# Esquema_v21.net
KiCad netlist of a schematic drawn in EAGLE
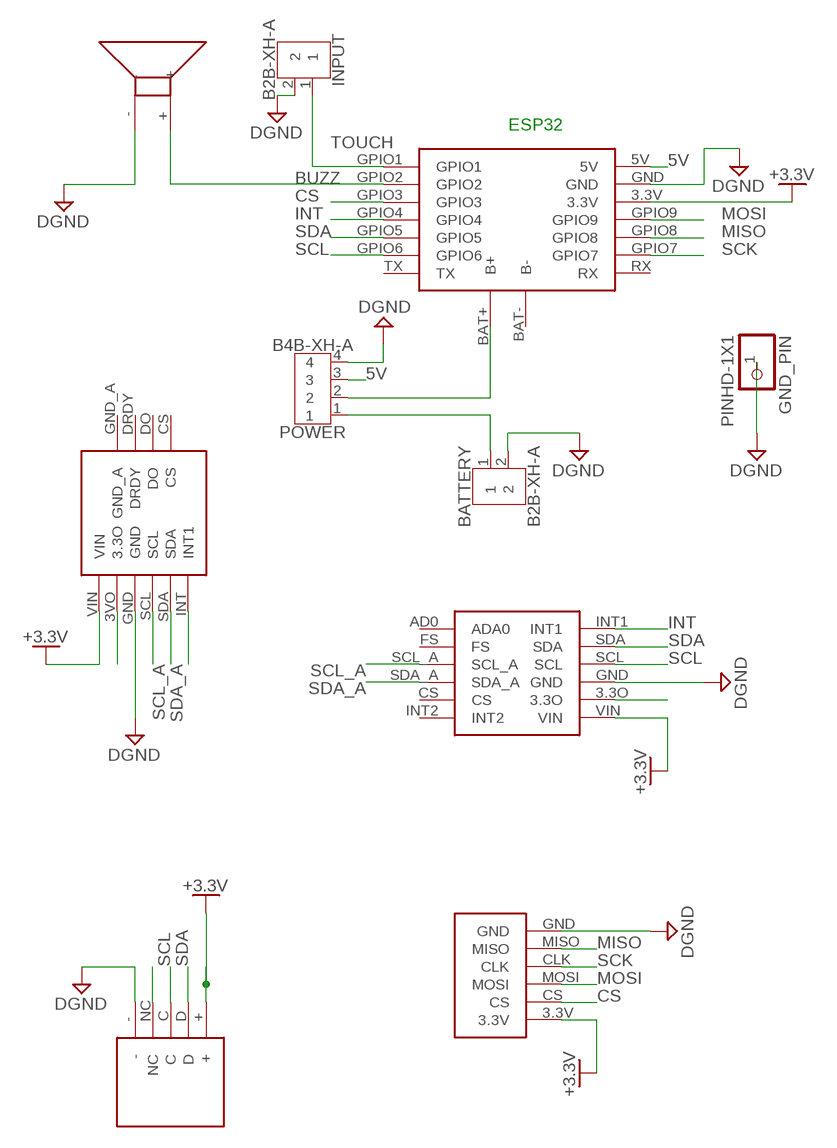
[diagram p0: schematic, sheet 1]

(export (version "E")
  (design (tool "Eeschema 10.0.6"))
  (components
    (comp (ref "BATTERY")
      (value "B2B-XH-A")
      (footprint "eagle-import:B2B-XH-A")
      (fields (field (name "MANUFACTURER") "JST Sales America Inc."))
      (libsource (lib "eagle-import") (part "B2B-XH-A"))
    )
    (comp (ref "GND_PIN")
      (value "PINHD-1X1")
      (footprint "eagle-import:1X01")
      (libsource (lib "eagle-import") (part "PINHD-1X1"))
    )
    (comp (ref "INPUT")
      (value "B2B-XH-A")
      (footprint "eagle-import:B2B-XH-A")
      (fields (field (name "MANUFACTURER") "JST Sales America Inc."))
      (libsource (lib "eagle-import") (part "B2B-XH-A"))
    )
    (comp (ref "POWER")
      (value "B4B-XH-A")
      (footprint "eagle-import:B4B-XH-A")
      (fields (field (name "MANUFACTURER") "JST Sales America Inc."))
      (libsource (lib "eagle-import") (part "B4B-XH-A"))
    )
    (comp (ref "U$1")
      (value "LIS3MDL")
      (footprint "eagle-import:LIS3MDL")
      (libsource (lib "eagle-import") (part "LIS3MDL"))
    )
    (comp (ref "U$2")
      (value "ICM20649")
      (footprint "eagle-import:ICM20649")
      (libsource (lib "eagle-import") (part "ICM20649"))
    )
    (comp (ref "U$3")
      (value "ESP32_SEEED_THP")
      (footprint "eagle-import:ESP32_SEEED_THP")
      (libsource (lib "eagle-import") (part "ESP32_SEEED_THP"))
    )
    (comp (ref "U$4")
      (value "DS3231_RPI")
      (footprint "eagle-import:DS3231_RPI")
      (libsource (lib "eagle-import") (part "DS3231_RPI"))
    )
    (comp (ref "U$5")
      (value "MICROSD_READER")
      (footprint "eagle-import:MICROSD_READER")
      (libsource (lib "eagle-import") (part "MICROSD_READER"))
    )
    (comp (ref "U$6")
      (value "BUZZER")
      (footprint "eagle-import:BUZZER")
      (libsource (lib "eagle-import") (part "BUZZER"))
    )
  )
  (nets
    (net (code "1") (name "+3.3V") (class "Default")
      (node (ref "U$1") (pin "VIN") (pinfunction "VIN_VIN") (pintype "bidirectional"))
      (node (ref "U$2") (pin "VIN") (pinfunction "VIN_VIN") (pintype "bidirectional"))
      (node (ref "U$3") (pin "3.3V") (pinfunction "3.3V_3.3V") (pintype "bidirectional"))
      (node (ref "U$4") (pin "+") (pinfunction "+_+") (pintype "bidirectional"))
      (node (ref "U$5") (pin "3.3V") (pinfunction "3.3V_3.3V") (pintype "bidirectional"))
    )
    (net (code "2") (name "/5V") (class "Default")
      (node (ref "POWER") (pin "3") (pinfunction "3_3") (pintype "bidirectional"))
      (node (ref "U$3") (pin "5V") (pinfunction "5V_5V") (pintype "bidirectional"))
    )
    (net (code "3") (name "/BUZZ") (class "Default")
      (node (ref "U$3") (pin "GPIO2") (pinfunction "GPIO2_GPIO2") (pintype "bidirectional"))
      (node (ref "U$6") (pin "+") (pinfunction "+_+") (pintype "bidirectional"))
    )
    (net (code "4") (name "/CS") (class "Default")
      (node (ref "U$3") (pin "GPIO3") (pinfunction "GPIO3_GPIO3") (pintype "bidirectional"))
      (node (ref "U$5") (pin "CS") (pinfunction "CS_CS") (pintype "bidirectional"))
    )
    (net (code "5") (name "/INT") (class "Default")
      (node (ref "U$2") (pin "INT1") (pinfunction "INT1_INT1") (pintype "bidirectional"))
      (node (ref "U$3") (pin "GPIO4") (pinfunction "GPIO4_GPIO4") (pintype "bidirectional"))
    )
    (net (code "6") (name "/MISO") (class "Default")
      (node (ref "U$3") (pin "GPIO8") (pinfunction "GPIO8_GPIO8") (pintype "bidirectional"))
      (node (ref "U$5") (pin "MISO") (pinfunction "MISO_MISO") (pintype "bidirectional"))
    )
    (net (code "7") (name "/MOSI") (class "Default")
      (node (ref "U$3") (pin "GPIO9") (pinfunction "GPIO9_GPIO9") (pintype "bidirectional"))
      (node (ref "U$5") (pin "MOSI") (pinfunction "MOSI_MOSI") (pintype "bidirectional"))
    )
    (net (code "8") (name "/SCK") (class "Default")
      (node (ref "U$3") (pin "GPIO7") (pinfunction "GPIO7_GPIO7") (pintype "bidirectional"))
      (node (ref "U$5") (pin "CLK") (pinfunction "CLK_CLK") (pintype "bidirectional"))
    )
    (net (code "9") (name "/SCL") (class "Default")
      (node (ref "U$2") (pin "SCL") (pinfunction "SCL_SCL") (pintype "bidirectional"))
      (node (ref "U$3") (pin "GPIO6") (pinfunction "GPIO6_GPIO6") (pintype "bidirectional"))
      (node (ref "U$4") (pin "C") (pinfunction "C_C") (pintype "bidirectional"))
    )
    (net (code "10") (name "/SCL_A") (class "Default")
      (node (ref "U$1") (pin "SCL") (pinfunction "SCL_SCL") (pintype "bidirectional"))
      (node (ref "U$2") (pin "SCL_A") (pinfunction "SCL_A_SCL_A") (pintype "bidirectional"))
    )
    (net (code "11") (name "/SDA") (class "Default")
      (node (ref "U$2") (pin "SDA") (pinfunction "SDA_SDA") (pintype "bidirectional"))
      (node (ref "U$3") (pin "GPIO5") (pinfunction "GPIO5_GPIO5") (pintype "bidirectional"))
      (node (ref "U$4") (pin "D") (pinfunction "D_D") (pintype "bidirectional"))
    )
    (net (code "12") (name "/SDA_A") (class "Default")
      (node (ref "U$1") (pin "SDA") (pinfunction "SDA_SDA") (pintype "bidirectional"))
      (node (ref "U$2") (pin "SDA_A") (pinfunction "SDA_A_SDA_A") (pintype "bidirectional"))
    )
    (net (code "13") (name "/TOUCH") (class "Default")
      (node (ref "INPUT") (pin "1") (pinfunction "1_1") (pintype "bidirectional"))
      (node (ref "U$3") (pin "GPIO1") (pinfunction "GPIO1_GPIO1") (pintype "bidirectional"))
    )
    (net (code "14") (name "DGND") (class "Default")
      (node (ref "BATTERY") (pin "2") (pinfunction "2_2") (pintype "bidirectional"))
      (node (ref "GND_PIN") (pin "1") (pinfunction "1_1") (pintype "passive"))
      (node (ref "INPUT") (pin "2") (pinfunction "2_2") (pintype "bidirectional"))
      (node (ref "POWER") (pin "4") (pinfunction "4_4") (pintype "bidirectional"))
      (node (ref "U$1") (pin "GND") (pinfunction "GND_GND") (pintype "bidirectional"))
      (node (ref "U$2") (pin "GND") (pinfunction "GND_GND") (pintype "bidirectional"))
      (node (ref "U$3") (pin "GND") (pinfunction "GND_GND") (pintype "bidirectional"))
      (node (ref "U$4") (pin "-") (pinfunction "-_-") (pintype "bidirectional"))
      (node (ref "U$5") (pin "GND") (pinfunction "GND_GND") (pintype "bidirectional"))
      (node (ref "U$6") (pin "-") (pinfunction "-_-") (pintype "bidirectional"))
    )
    (net (code "15") (name "Net-(BATTERY-Pad1)") (class "Default")
      (node (ref "BATTERY") (pin "1") (pinfunction "1_1") (pintype "bidirectional"))
      (node (ref "POWER") (pin "1") (pinfunction "1_1") (pintype "bidirectional"))
    )
    (net (code "16") (name "Net-(U$3-B+)") (class "Default")
      (node (ref "POWER") (pin "2") (pinfunction "2_2") (pintype "bidirectional"))
      (node (ref "U$3") (pin "BAT+") (pinfunction "B+_BAT+") (pintype "bidirectional"))
    )
    (net (code "17") (name "unconnected-(U$1-3.3O-Pad3VO)") (class "Default")
      (node (ref "U$1") (pin "3VO") (pinfunction "3.3O_3VO") (pintype "bidirectional"))
    )
    (net (code "18") (name "unconnected-(U$1-INT1-PadINT)") (class "Default")
      (node (ref "U$1") (pin "INT") (pinfunction "INT1_INT") (pintype "bidirectional"))
    )
    (net (code "19") (name "unconnected-(U$1-PadCS)") (class "Default")
      (node (ref "U$1") (pin "CS") (pinfunction "CS_CS") (pintype "bidirectional"))
    )
    (net (code "20") (name "unconnected-(U$1-PadDO)") (class "Default")
      (node (ref "U$1") (pin "DO") (pinfunction "DO_DO") (pintype "bidirectional"))
    )
    (net (code "21") (name "unconnected-(U$1-PadDRDY)") (class "Default")
      (node (ref "U$1") (pin "DRDY") (pinfunction "DRDY_DRDY") (pintype "bidirectional"))
    )
    (net (code "22") (name "unconnected-(U$1-PadGND_A)") (class "Default")
      (node (ref "U$1") (pin "GND_A") (pinfunction "GND_A_GND_A") (pintype "bidirectional"))
    )
    (net (code "23") (name "unconnected-(U$2-ADA0-PadAD0)") (class "Default")
      (node (ref "U$2") (pin "AD0") (pinfunction "ADA0_AD0") (pintype "bidirectional"))
    )
    (net (code "24") (name "unconnected-(U$2-Pad3.3O)") (class "Default")
      (node (ref "U$2") (pin "3.3O") (pinfunction "3.3O_3.3O") (pintype "bidirectional"))
    )
    (net (code "25") (name "unconnected-(U$2-PadCS)") (class "Default")
      (node (ref "U$2") (pin "CS") (pinfunction "CS_CS") (pintype "bidirectional"))
    )
    (net (code "26") (name "unconnected-(U$2-PadFS)") (class "Default")
      (node (ref "U$2") (pin "FS") (pinfunction "FS_FS") (pintype "bidirectional"))
    )
    (net (code "27") (name "unconnected-(U$2-PadINT2)") (class "Default")
      (node (ref "U$2") (pin "INT2") (pinfunction "INT2_INT2") (pintype "bidirectional"))
    )
    (net (code "28") (name "unconnected-(U$3-B--PadBAT-)") (class "Default")
      (node (ref "U$3") (pin "BAT-") (pinfunction "B-_BAT-") (pintype "bidirectional"))
    )
    (net (code "29") (name "unconnected-(U$3-PadRX)") (class "Default")
      (node (ref "U$3") (pin "RX") (pinfunction "RX_RX") (pintype "bidirectional"))
    )
    (net (code "30") (name "unconnected-(U$3-PadTX)") (class "Default")
      (node (ref "U$3") (pin "TX") (pinfunction "TX_TX") (pintype "bidirectional"))
    )
    (net (code "31") (name "unconnected-(U$4-PadNC)") (class "Default")
      (node (ref "U$4") (pin "NC") (pinfunction "NC_NC") (pintype "bidirectional"))
    )
  )
)
